# shieldrasp3.net
KiCad netlist of a schematic drawn in EAGLE
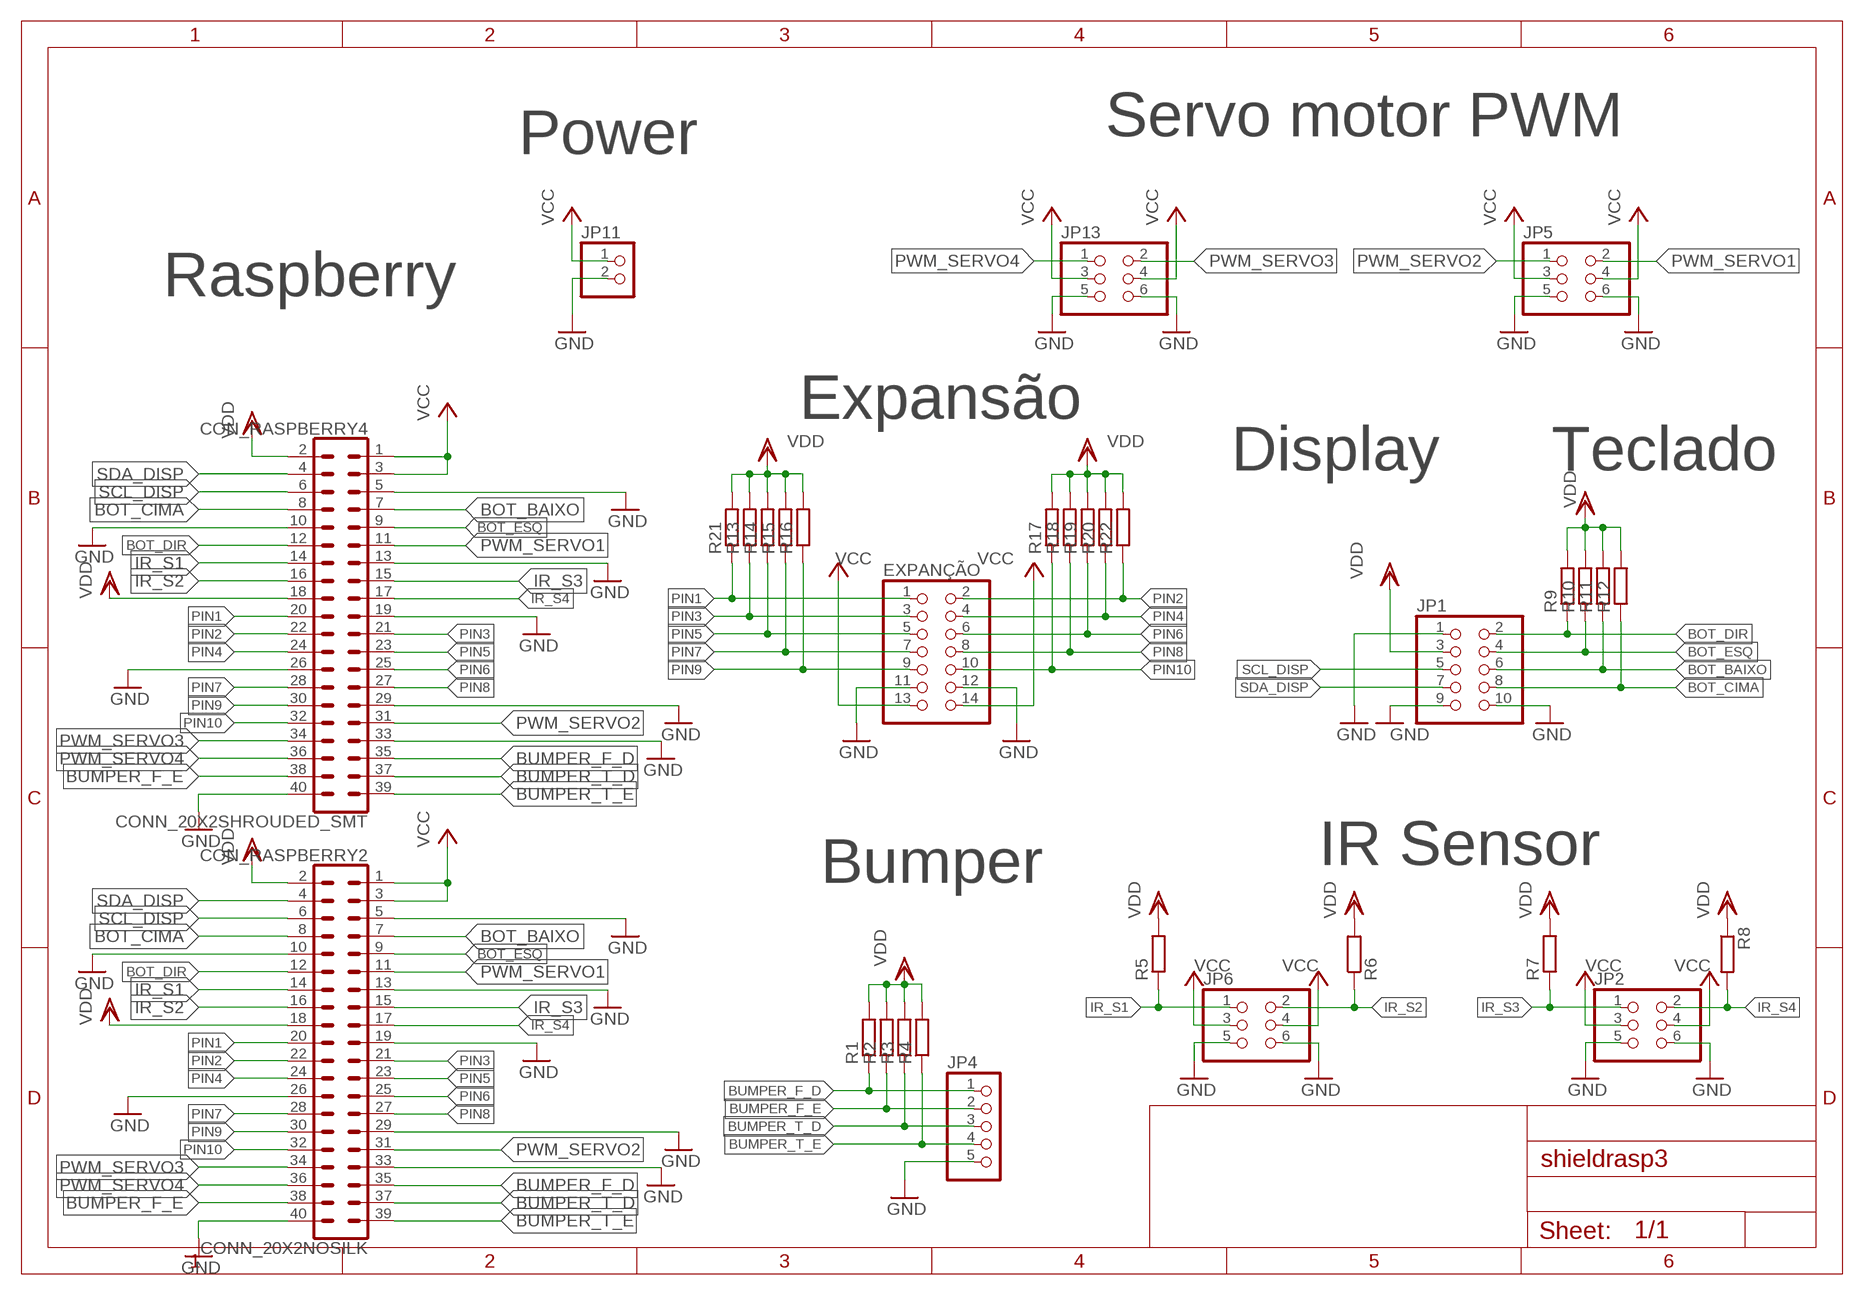
[diagram p0: schematic, sheet 1]

(export (version "E")
  (design (tool "Eeschema 10.0.6"))
  (components
    (comp (ref "CON_RASPBERRY2")
      (value "CONN_20X2NOSILK")
      (footprint "eagle-import:2X20_NOSILK")
      (libsource (lib "eagle-import") (part "CONN_20X2NOSILK"))
    )
    (comp (ref "CON_RASPBERRY4")
      (value "CONN_20X2SHROUDED_SMT")
      (footprint "eagle-import:2X20_SHROUDED_SMT")
      (libsource (lib "eagle-import") (part "CONN_20X2SHROUDED_SMT"))
    )
    (comp (ref "EXPANÇÃO")
      (value "PINHD-2X7")
      (footprint "eagle-import:2X07")
      (libsource (lib "eagle-import") (part "PINHD-2X7"))
    )
    (comp (ref "JP1")
      (value "PINHD-2X5")
      (footprint "eagle-import:2X05")
      (libsource (lib "eagle-import") (part "PINHD-2X5"))
    )
    (comp (ref "JP2")
      (value "PINHD-2X3")
      (footprint "eagle-import:2X03")
      (libsource (lib "eagle-import") (part "PINHD-2X3"))
    )
    (comp (ref "JP4")
      (value "PINHD-1X5")
      (footprint "eagle-import:1X05")
      (libsource (lib "eagle-import") (part "PINHD-1X5"))
    )
    (comp (ref "JP5")
      (value "PINHD-2X3")
      (footprint "eagle-import:2X03")
      (libsource (lib "eagle-import") (part "PINHD-2X3"))
    )
    (comp (ref "JP6")
      (value "PINHD-2X3")
      (footprint "eagle-import:2X03")
      (libsource (lib "eagle-import") (part "PINHD-2X3"))
    )
    (comp (ref "JP11")
      (value "PINHD-1X2")
      (footprint "eagle-import:1X02")
      (libsource (lib "eagle-import") (part "PINHD-1X2"))
    )
    (comp (ref "JP13")
      (value "PINHD-2X3")
      (footprint "eagle-import:2X03")
      (libsource (lib "eagle-import") (part "PINHD-2X3"))
    )
    (comp (ref "R1")
      (value "R-EU_M0805")
      (footprint "eagle-import:M0805")
      (libsource (lib "eagle-import") (part "R-EU_M0805"))
    )
    (comp (ref "R2")
      (value "R-EU_M0805")
      (footprint "eagle-import:M0805")
      (libsource (lib "eagle-import") (part "R-EU_M0805"))
    )
    (comp (ref "R3")
      (value "R-EU_M0805")
      (footprint "eagle-import:M0805")
      (libsource (lib "eagle-import") (part "R-EU_M0805"))
    )
    (comp (ref "R4")
      (value "R-EU_M0805")
      (footprint "eagle-import:M0805")
      (libsource (lib "eagle-import") (part "R-EU_M0805"))
    )
    (comp (ref "R5")
      (value "R-EU_M0805")
      (footprint "eagle-import:M0805")
      (libsource (lib "eagle-import") (part "R-EU_M0805"))
    )
    (comp (ref "R6")
      (value "R-EU_M0805")
      (footprint "eagle-import:M0805")
      (libsource (lib "eagle-import") (part "R-EU_M0805"))
    )
    (comp (ref "R7")
      (value "R-EU_M0805")
      (footprint "eagle-import:M0805")
      (libsource (lib "eagle-import") (part "R-EU_M0805"))
    )
    (comp (ref "R8")
      (value "R-EU_M0805")
      (footprint "eagle-import:M0805")
      (libsource (lib "eagle-import") (part "R-EU_M0805"))
    )
    (comp (ref "R9")
      (value "R-EU_M0805")
      (footprint "eagle-import:M0805")
      (libsource (lib "eagle-import") (part "R-EU_M0805"))
    )
    (comp (ref "R10")
      (value "R-EU_M0805")
      (footprint "eagle-import:M0805")
      (libsource (lib "eagle-import") (part "R-EU_M0805"))
    )
    (comp (ref "R11")
      (value "R-EU_M0805")
      (footprint "eagle-import:M0805")
      (libsource (lib "eagle-import") (part "R-EU_M0805"))
    )
    (comp (ref "R12")
      (value "R-EU_M0805")
      (footprint "eagle-import:M0805")
      (libsource (lib "eagle-import") (part "R-EU_M0805"))
    )
    (comp (ref "R13")
      (value "R-EU_M0805")
      (footprint "eagle-import:M0805")
      (libsource (lib "eagle-import") (part "R-EU_M0805"))
    )
    (comp (ref "R14")
      (value "R-EU_M0805")
      (footprint "eagle-import:M0805")
      (libsource (lib "eagle-import") (part "R-EU_M0805"))
    )
    (comp (ref "R15")
      (value "R-EU_M0805")
      (footprint "eagle-import:M0805")
      (libsource (lib "eagle-import") (part "R-EU_M0805"))
    )
    (comp (ref "R16")
      (value "R-EU_M0805")
      (footprint "eagle-import:M0805")
      (libsource (lib "eagle-import") (part "R-EU_M0805"))
    )
    (comp (ref "R17")
      (value "R-EU_M0805")
      (footprint "eagle-import:M0805")
      (libsource (lib "eagle-import") (part "R-EU_M0805"))
    )
    (comp (ref "R18")
      (value "R-EU_M0805")
      (footprint "eagle-import:M0805")
      (libsource (lib "eagle-import") (part "R-EU_M0805"))
    )
    (comp (ref "R19")
      (value "R-EU_M0805")
      (footprint "eagle-import:M0805")
      (libsource (lib "eagle-import") (part "R-EU_M0805"))
    )
    (comp (ref "R20")
      (value "R-EU_M0805")
      (footprint "eagle-import:M0805")
      (libsource (lib "eagle-import") (part "R-EU_M0805"))
    )
    (comp (ref "R21")
      (value "R-EU_M0805")
      (footprint "eagle-import:M0805")
      (libsource (lib "eagle-import") (part "R-EU_M0805"))
    )
    (comp (ref "R22")
      (value "R-EU_M0805")
      (footprint "eagle-import:M0805")
      (libsource (lib "eagle-import") (part "R-EU_M0805"))
    )
  )
  (nets
    (net (code "1") (name "BOT_BAIXO") (class "Default")
      (node (ref "CON_RASPBERRY2") (pin "7") (pinfunction "7_7") (pintype "passive"))
      (node (ref "CON_RASPBERRY4") (pin "7") (pinfunction "7_7") (pintype "passive"))
      (node (ref "JP1") (pin "6") (pinfunction "6_6") (pintype "passive"))
      (node (ref "R11") (pin "1") (pinfunction "1_1") (pintype "passive"))
    )
    (net (code "2") (name "BOT_CIMA") (class "Default")
      (node (ref "CON_RASPBERRY2") (pin "8") (pinfunction "8_8") (pintype "passive"))
      (node (ref "CON_RASPBERRY4") (pin "8") (pinfunction "8_8") (pintype "passive"))
      (node (ref "JP1") (pin "8") (pinfunction "8_8") (pintype "passive"))
      (node (ref "R12") (pin "1") (pinfunction "1_1") (pintype "passive"))
    )
    (net (code "3") (name "BOT_DIR") (class "Default")
      (node (ref "CON_RASPBERRY2") (pin "12") (pinfunction "12_12") (pintype "passive"))
      (node (ref "CON_RASPBERRY4") (pin "12") (pinfunction "12_12") (pintype "passive"))
      (node (ref "JP1") (pin "2") (pinfunction "2_2") (pintype "passive"))
      (node (ref "R9") (pin "1") (pinfunction "1_1") (pintype "passive"))
    )
    (net (code "4") (name "BOT_ESQ") (class "Default")
      (node (ref "CON_RASPBERRY2") (pin "9") (pinfunction "9_9") (pintype "passive"))
      (node (ref "CON_RASPBERRY4") (pin "9") (pinfunction "9_9") (pintype "passive"))
      (node (ref "JP1") (pin "4") (pinfunction "4_4") (pintype "passive"))
      (node (ref "R10") (pin "1") (pinfunction "1_1") (pintype "passive"))
    )
    (net (code "5") (name "BUMPER_F_D") (class "Default")
      (node (ref "CON_RASPBERRY2") (pin "35") (pinfunction "35_35") (pintype "passive"))
      (node (ref "CON_RASPBERRY4") (pin "35") (pinfunction "35_35") (pintype "passive"))
      (node (ref "JP4") (pin "1") (pinfunction "1_1") (pintype "passive"))
      (node (ref "R1") (pin "1") (pinfunction "1_1") (pintype "passive"))
    )
    (net (code "6") (name "BUMPER_F_E") (class "Default")
      (node (ref "CON_RASPBERRY2") (pin "38") (pinfunction "38_38") (pintype "passive"))
      (node (ref "CON_RASPBERRY4") (pin "38") (pinfunction "38_38") (pintype "passive"))
      (node (ref "JP4") (pin "2") (pinfunction "2_2") (pintype "passive"))
      (node (ref "R2") (pin "1") (pinfunction "1_1") (pintype "passive"))
    )
    (net (code "7") (name "BUMPER_T_D") (class "Default")
      (node (ref "CON_RASPBERRY2") (pin "37") (pinfunction "37_37") (pintype "passive"))
      (node (ref "CON_RASPBERRY4") (pin "37") (pinfunction "37_37") (pintype "passive"))
      (node (ref "JP4") (pin "3") (pinfunction "3_3") (pintype "passive"))
      (node (ref "R3") (pin "1") (pinfunction "1_1") (pintype "passive"))
    )
    (net (code "8") (name "BUMPER_T_E") (class "Default")
      (node (ref "CON_RASPBERRY2") (pin "39") (pinfunction "39_39") (pintype "passive"))
      (node (ref "CON_RASPBERRY4") (pin "39") (pinfunction "39_39") (pintype "passive"))
      (node (ref "JP4") (pin "4") (pinfunction "4_4") (pintype "passive"))
      (node (ref "R4") (pin "1") (pinfunction "1_1") (pintype "passive"))
    )
    (net (code "9") (name "GND") (class "Default")
      (node (ref "CON_RASPBERRY2") (pin "10") (pinfunction "10_10") (pintype "passive"))
      (node (ref "CON_RASPBERRY2") (pin "13") (pinfunction "13_13") (pintype "passive"))
      (node (ref "CON_RASPBERRY2") (pin "19") (pinfunction "19_19") (pintype "passive"))
      (node (ref "CON_RASPBERRY2") (pin "26") (pinfunction "26_26") (pintype "passive"))
      (node (ref "CON_RASPBERRY2") (pin "29") (pinfunction "29_29") (pintype "passive"))
      (node (ref "CON_RASPBERRY2") (pin "33") (pinfunction "33_33") (pintype "passive"))
      (node (ref "CON_RASPBERRY2") (pin "40") (pinfunction "40_40") (pintype "passive"))
      (node (ref "CON_RASPBERRY2") (pin "5") (pinfunction "5_5") (pintype "passive"))
      (node (ref "CON_RASPBERRY4") (pin "10") (pinfunction "10_10") (pintype "passive"))
      (node (ref "CON_RASPBERRY4") (pin "13") (pinfunction "13_13") (pintype "passive"))
      (node (ref "CON_RASPBERRY4") (pin "19") (pinfunction "19_19") (pintype "passive"))
      (node (ref "CON_RASPBERRY4") (pin "26") (pinfunction "26_26") (pintype "passive"))
      (node (ref "CON_RASPBERRY4") (pin "29") (pinfunction "29_29") (pintype "passive"))
      (node (ref "CON_RASPBERRY4") (pin "33") (pinfunction "33_33") (pintype "passive"))
      (node (ref "CON_RASPBERRY4") (pin "40") (pinfunction "40_40") (pintype "passive"))
      (node (ref "CON_RASPBERRY4") (pin "5") (pinfunction "5_5") (pintype "passive"))
      (node (ref "EXPANÇÃO") (pin "11") (pinfunction "11_11") (pintype "passive"))
      (node (ref "EXPANÇÃO") (pin "12") (pinfunction "12_12") (pintype "passive"))
      (node (ref "JP1") (pin "1") (pinfunction "1_1") (pintype "passive"))
      (node (ref "JP1") (pin "10") (pinfunction "10_10") (pintype "passive"))
      (node (ref "JP1") (pin "9") (pinfunction "9_9") (pintype "passive"))
      (node (ref "JP11") (pin "2") (pinfunction "2_2") (pintype "passive"))
      (node (ref "JP13") (pin "5") (pinfunction "5_5") (pintype "passive"))
      (node (ref "JP13") (pin "6") (pinfunction "6_6") (pintype "passive"))
      (node (ref "JP2") (pin "5") (pinfunction "5_5") (pintype "passive"))
      (node (ref "JP2") (pin "6") (pinfunction "6_6") (pintype "passive"))
      (node (ref "JP4") (pin "5") (pinfunction "5_5") (pintype "passive"))
      (node (ref "JP5") (pin "5") (pinfunction "5_5") (pintype "passive"))
      (node (ref "JP5") (pin "6") (pinfunction "6_6") (pintype "passive"))
      (node (ref "JP6") (pin "5") (pinfunction "5_5") (pintype "passive"))
      (node (ref "JP6") (pin "6") (pinfunction "6_6") (pintype "passive"))
    )
    (net (code "10") (name "IR_S1") (class "Default")
      (node (ref "CON_RASPBERRY2") (pin "14") (pinfunction "14_14") (pintype "passive"))
      (node (ref "CON_RASPBERRY4") (pin "14") (pinfunction "14_14") (pintype "passive"))
      (node (ref "JP6") (pin "1") (pinfunction "1_1") (pintype "passive"))
      (node (ref "R5") (pin "1") (pinfunction "1_1") (pintype "passive"))
    )
    (net (code "11") (name "IR_S2") (class "Default")
      (node (ref "CON_RASPBERRY2") (pin "16") (pinfunction "16_16") (pintype "passive"))
      (node (ref "CON_RASPBERRY4") (pin "16") (pinfunction "16_16") (pintype "passive"))
      (node (ref "JP6") (pin "2") (pinfunction "2_2") (pintype "passive"))
      (node (ref "R6") (pin "1") (pinfunction "1_1") (pintype "passive"))
    )
    (net (code "12") (name "IR_S3") (class "Default")
      (node (ref "CON_RASPBERRY2") (pin "15") (pinfunction "15_15") (pintype "passive"))
      (node (ref "CON_RASPBERRY4") (pin "15") (pinfunction "15_15") (pintype "passive"))
      (node (ref "JP2") (pin "1") (pinfunction "1_1") (pintype "passive"))
      (node (ref "R7") (pin "1") (pinfunction "1_1") (pintype "passive"))
    )
    (net (code "13") (name "IR_S4") (class "Default")
      (node (ref "CON_RASPBERRY2") (pin "17") (pinfunction "17_17") (pintype "passive"))
      (node (ref "CON_RASPBERRY4") (pin "17") (pinfunction "17_17") (pintype "passive"))
      (node (ref "JP2") (pin "2") (pinfunction "2_2") (pintype "passive"))
      (node (ref "R8") (pin "2") (pinfunction "2_2") (pintype "passive"))
    )
    (net (code "14") (name "PIN1") (class "Default")
      (node (ref "CON_RASPBERRY2") (pin "20") (pinfunction "20_20") (pintype "passive"))
      (node (ref "CON_RASPBERRY4") (pin "20") (pinfunction "20_20") (pintype "passive"))
      (node (ref "EXPANÇÃO") (pin "1") (pinfunction "1_1") (pintype "passive"))
      (node (ref "R21") (pin "1") (pinfunction "1_1") (pintype "passive"))
    )
    (net (code "15") (name "PIN2") (class "Default")
      (node (ref "CON_RASPBERRY2") (pin "22") (pinfunction "22_22") (pintype "passive"))
      (node (ref "CON_RASPBERRY4") (pin "22") (pinfunction "22_22") (pintype "passive"))
      (node (ref "EXPANÇÃO") (pin "2") (pinfunction "2_2") (pintype "passive"))
      (node (ref "R22") (pin "1") (pinfunction "1_1") (pintype "passive"))
    )
    (net (code "16") (name "PIN3") (class "Default")
      (node (ref "CON_RASPBERRY2") (pin "21") (pinfunction "21_21") (pintype "passive"))
      (node (ref "CON_RASPBERRY4") (pin "21") (pinfunction "21_21") (pintype "passive"))
      (node (ref "EXPANÇÃO") (pin "3") (pinfunction "3_3") (pintype "passive"))
      (node (ref "R13") (pin "1") (pinfunction "1_1") (pintype "passive"))
    )
    (net (code "17") (name "PIN4") (class "Default")
      (node (ref "CON_RASPBERRY2") (pin "24") (pinfunction "24_24") (pintype "passive"))
      (node (ref "CON_RASPBERRY4") (pin "24") (pinfunction "24_24") (pintype "passive"))
      (node (ref "EXPANÇÃO") (pin "4") (pinfunction "4_4") (pintype "passive"))
      (node (ref "R20") (pin "1") (pinfunction "1_1") (pintype "passive"))
    )
    (net (code "18") (name "PIN5") (class "Default")
      (node (ref "CON_RASPBERRY2") (pin "23") (pinfunction "23_23") (pintype "passive"))
      (node (ref "CON_RASPBERRY4") (pin "23") (pinfunction "23_23") (pintype "passive"))
      (node (ref "EXPANÇÃO") (pin "5") (pinfunction "5_5") (pintype "passive"))
      (node (ref "R14") (pin "1") (pinfunction "1_1") (pintype "passive"))
    )
    (net (code "19") (name "PIN6") (class "Default")
      (node (ref "CON_RASPBERRY2") (pin "25") (pinfunction "25_25") (pintype "passive"))
      (node (ref "CON_RASPBERRY4") (pin "25") (pinfunction "25_25") (pintype "passive"))
      (node (ref "EXPANÇÃO") (pin "6") (pinfunction "6_6") (pintype "passive"))
      (node (ref "R19") (pin "1") (pinfunction "1_1") (pintype "passive"))
    )
    (net (code "20") (name "PIN7") (class "Default")
      (node (ref "CON_RASPBERRY2") (pin "28") (pinfunction "28_28") (pintype "passive"))
      (node (ref "CON_RASPBERRY4") (pin "28") (pinfunction "28_28") (pintype "passive"))
      (node (ref "EXPANÇÃO") (pin "7") (pinfunction "7_7") (pintype "passive"))
      (node (ref "R15") (pin "1") (pinfunction "1_1") (pintype "passive"))
    )
    (net (code "21") (name "PIN8") (class "Default")
      (node (ref "CON_RASPBERRY2") (pin "27") (pinfunction "27_27") (pintype "passive"))
      (node (ref "CON_RASPBERRY4") (pin "27") (pinfunction "27_27") (pintype "passive"))
      (node (ref "EXPANÇÃO") (pin "8") (pinfunction "8_8") (pintype "passive"))
      (node (ref "R18") (pin "1") (pinfunction "1_1") (pintype "passive"))
    )
    (net (code "22") (name "PIN9") (class "Default")
      (node (ref "CON_RASPBERRY2") (pin "30") (pinfunction "30_30") (pintype "passive"))
      (node (ref "CON_RASPBERRY4") (pin "30") (pinfunction "30_30") (pintype "passive"))
      (node (ref "EXPANÇÃO") (pin "9") (pinfunction "9_9") (pintype "passive"))
      (node (ref "R16") (pin "1") (pinfunction "1_1") (pintype "passive"))
    )
    (net (code "23") (name "PIN10") (class "Default")
      (node (ref "CON_RASPBERRY2") (pin "32") (pinfunction "32_32") (pintype "passive"))
      (node (ref "CON_RASPBERRY4") (pin "32") (pinfunction "32_32") (pintype "passive"))
      (node (ref "EXPANÇÃO") (pin "10") (pinfunction "10_10") (pintype "passive"))
      (node (ref "R17") (pin "1") (pinfunction "1_1") (pintype "passive"))
    )
    (net (code "24") (name "PWM_SERVO1") (class "Default")
      (node (ref "CON_RASPBERRY2") (pin "11") (pinfunction "11_11") (pintype "passive"))
      (node (ref "CON_RASPBERRY4") (pin "11") (pinfunction "11_11") (pintype "passive"))
      (node (ref "JP5") (pin "2") (pinfunction "2_2") (pintype "passive"))
    )
    (net (code "25") (name "PWM_SERVO2") (class "Default")
      (node (ref "CON_RASPBERRY2") (pin "31") (pinfunction "31_31") (pintype "passive"))
      (node (ref "CON_RASPBERRY4") (pin "31") (pinfunction "31_31") (pintype "passive"))
      (node (ref "JP5") (pin "1") (pinfunction "1_1") (pintype "passive"))
    )
    (net (code "26") (name "PWM_SERVO3") (class "Default")
      (node (ref "CON_RASPBERRY2") (pin "34") (pinfunction "34_34") (pintype "passive"))
      (node (ref "CON_RASPBERRY4") (pin "34") (pinfunction "34_34") (pintype "passive"))
      (node (ref "JP13") (pin "2") (pinfunction "2_2") (pintype "passive"))
    )
    (net (code "27") (name "PWM_SERVO4") (class "Default")
      (node (ref "CON_RASPBERRY2") (pin "36") (pinfunction "36_36") (pintype "passive"))
      (node (ref "CON_RASPBERRY4") (pin "36") (pinfunction "36_36") (pintype "passive"))
      (node (ref "JP13") (pin "1") (pinfunction "1_1") (pintype "passive"))
    )
    (net (code "28") (name "SCL_DISP") (class "Default")
      (node (ref "CON_RASPBERRY2") (pin "6") (pinfunction "6_6") (pintype "passive"))
      (node (ref "CON_RASPBERRY4") (pin "6") (pinfunction "6_6") (pintype "passive"))
      (node (ref "JP1") (pin "5") (pinfunction "5_5") (pintype "passive"))
    )
    (net (code "29") (name "SDA_DISP") (class "Default")
      (node (ref "CON_RASPBERRY2") (pin "4") (pinfunction "4_4") (pintype "passive"))
      (node (ref "CON_RASPBERRY4") (pin "4") (pinfunction "4_4") (pintype "passive"))
      (node (ref "JP1") (pin "7") (pinfunction "7_7") (pintype "passive"))
    )
    (net (code "30") (name "VCC") (class "Default")
      (node (ref "CON_RASPBERRY2") (pin "1") (pinfunction "1_1") (pintype "passive"))
      (node (ref "CON_RASPBERRY2") (pin "3") (pinfunction "3_3") (pintype "passive"))
      (node (ref "CON_RASPBERRY4") (pin "1") (pinfunction "1_1") (pintype "passive"))
      (node (ref "CON_RASPBERRY4") (pin "3") (pinfunction "3_3") (pintype "passive"))
      (node (ref "EXPANÇÃO") (pin "13") (pinfunction "13_13") (pintype "passive"))
      (node (ref "EXPANÇÃO") (pin "14") (pinfunction "14_14") (pintype "passive"))
      (node (ref "JP11") (pin "1") (pinfunction "1_1") (pintype "passive"))
      (node (ref "JP13") (pin "3") (pinfunction "3_3") (pintype "passive"))
      (node (ref "JP13") (pin "4") (pinfunction "4_4") (pintype "passive"))
      (node (ref "JP2") (pin "3") (pinfunction "3_3") (pintype "passive"))
      (node (ref "JP2") (pin "4") (pinfunction "4_4") (pintype "passive"))
      (node (ref "JP5") (pin "3") (pinfunction "3_3") (pintype "passive"))
      (node (ref "JP5") (pin "4") (pinfunction "4_4") (pintype "passive"))
      (node (ref "JP6") (pin "3") (pinfunction "3_3") (pintype "passive"))
      (node (ref "JP6") (pin "4") (pinfunction "4_4") (pintype "passive"))
    )
    (net (code "31") (name "VDD") (class "Default")
      (node (ref "CON_RASPBERRY2") (pin "18") (pinfunction "18_18") (pintype "passive"))
      (node (ref "CON_RASPBERRY2") (pin "2") (pinfunction "2_2") (pintype "passive"))
      (node (ref "CON_RASPBERRY4") (pin "18") (pinfunction "18_18") (pintype "passive"))
      (node (ref "CON_RASPBERRY4") (pin "2") (pinfunction "2_2") (pintype "passive"))
      (node (ref "JP1") (pin "3") (pinfunction "3_3") (pintype "passive"))
      (node (ref "R1") (pin "2") (pinfunction "2_2") (pintype "passive"))
      (node (ref "R10") (pin "2") (pinfunction "2_2") (pintype "passive"))
      (node (ref "R11") (pin "2") (pinfunction "2_2") (pintype "passive"))
      (node (ref "R12") (pin "2") (pinfunction "2_2") (pintype "passive"))
      (node (ref "R13") (pin "2") (pinfunction "2_2") (pintype "passive"))
      (node (ref "R14") (pin "2") (pinfunction "2_2") (pintype "passive"))
      (node (ref "R15") (pin "2") (pinfunction "2_2") (pintype "passive"))
      (node (ref "R16") (pin "2") (pinfunction "2_2") (pintype "passive"))
      (node (ref "R17") (pin "2") (pinfunction "2_2") (pintype "passive"))
      (node (ref "R18") (pin "2") (pinfunction "2_2") (pintype "passive"))
      (node (ref "R19") (pin "2") (pinfunction "2_2") (pintype "passive"))
      (node (ref "R2") (pin "2") (pinfunction "2_2") (pintype "passive"))
      (node (ref "R20") (pin "2") (pinfunction "2_2") (pintype "passive"))
      (node (ref "R21") (pin "2") (pinfunction "2_2") (pintype "passive"))
      (node (ref "R22") (pin "2") (pinfunction "2_2") (pintype "passive"))
      (node (ref "R3") (pin "2") (pinfunction "2_2") (pintype "passive"))
      (node (ref "R4") (pin "2") (pinfunction "2_2") (pintype "passive"))
      (node (ref "R5") (pin "2") (pinfunction "2_2") (pintype "passive"))
      (node (ref "R6") (pin "2") (pinfunction "2_2") (pintype "passive"))
      (node (ref "R7") (pin "2") (pinfunction "2_2") (pintype "passive"))
      (node (ref "R8") (pin "1") (pinfunction "1_1") (pintype "passive"))
      (node (ref "R9") (pin "2") (pinfunction "2_2") (pintype "passive"))
    )
  )
)
